# CAMERA.net
KiCad netlist of a schematic drawn in Altium Designer
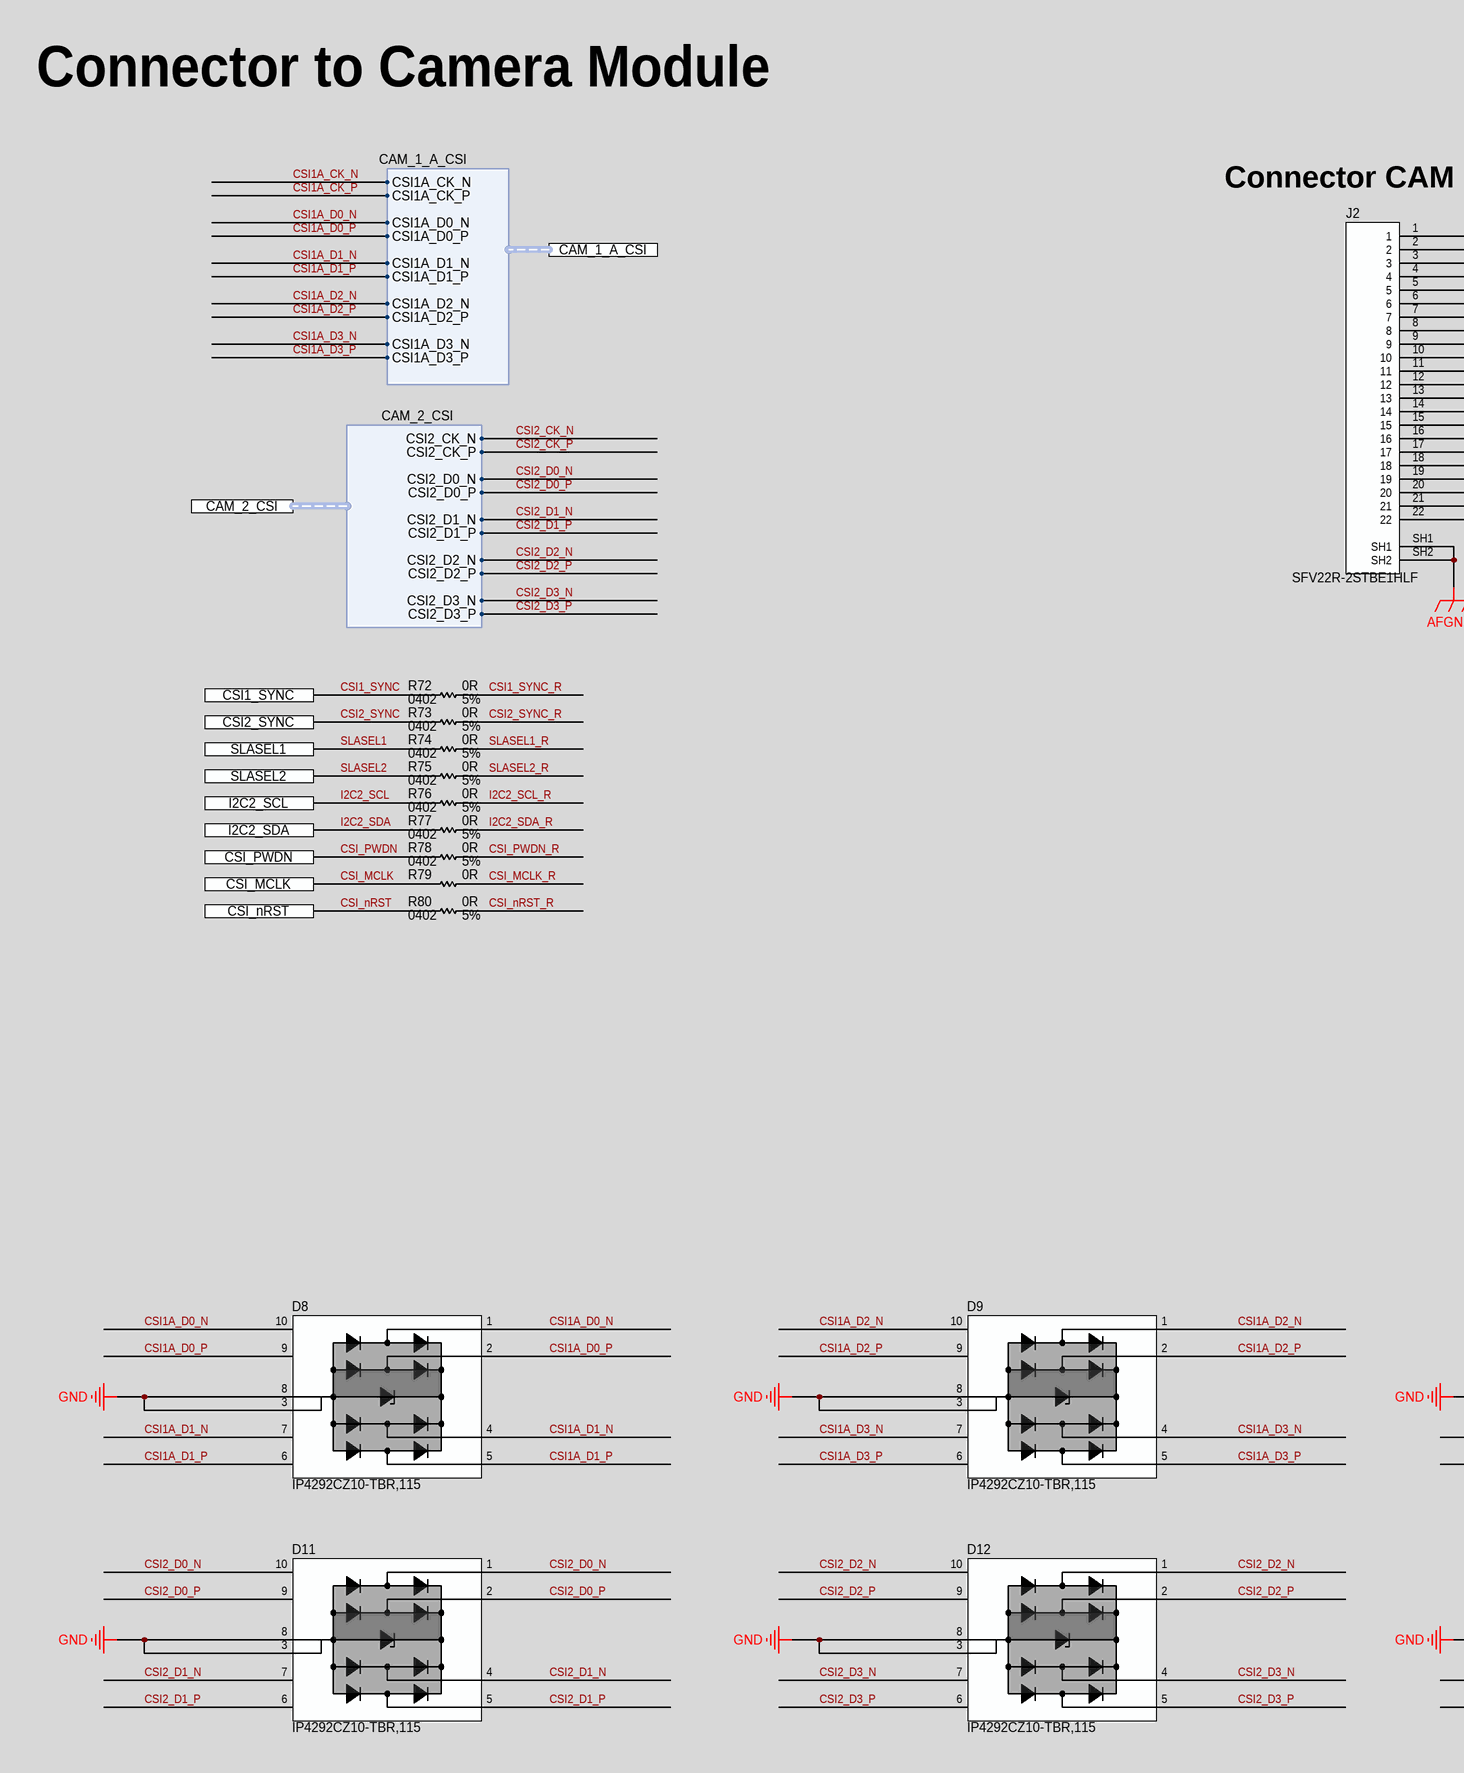
[diagram p0: CAMERA.SchDoc, left]
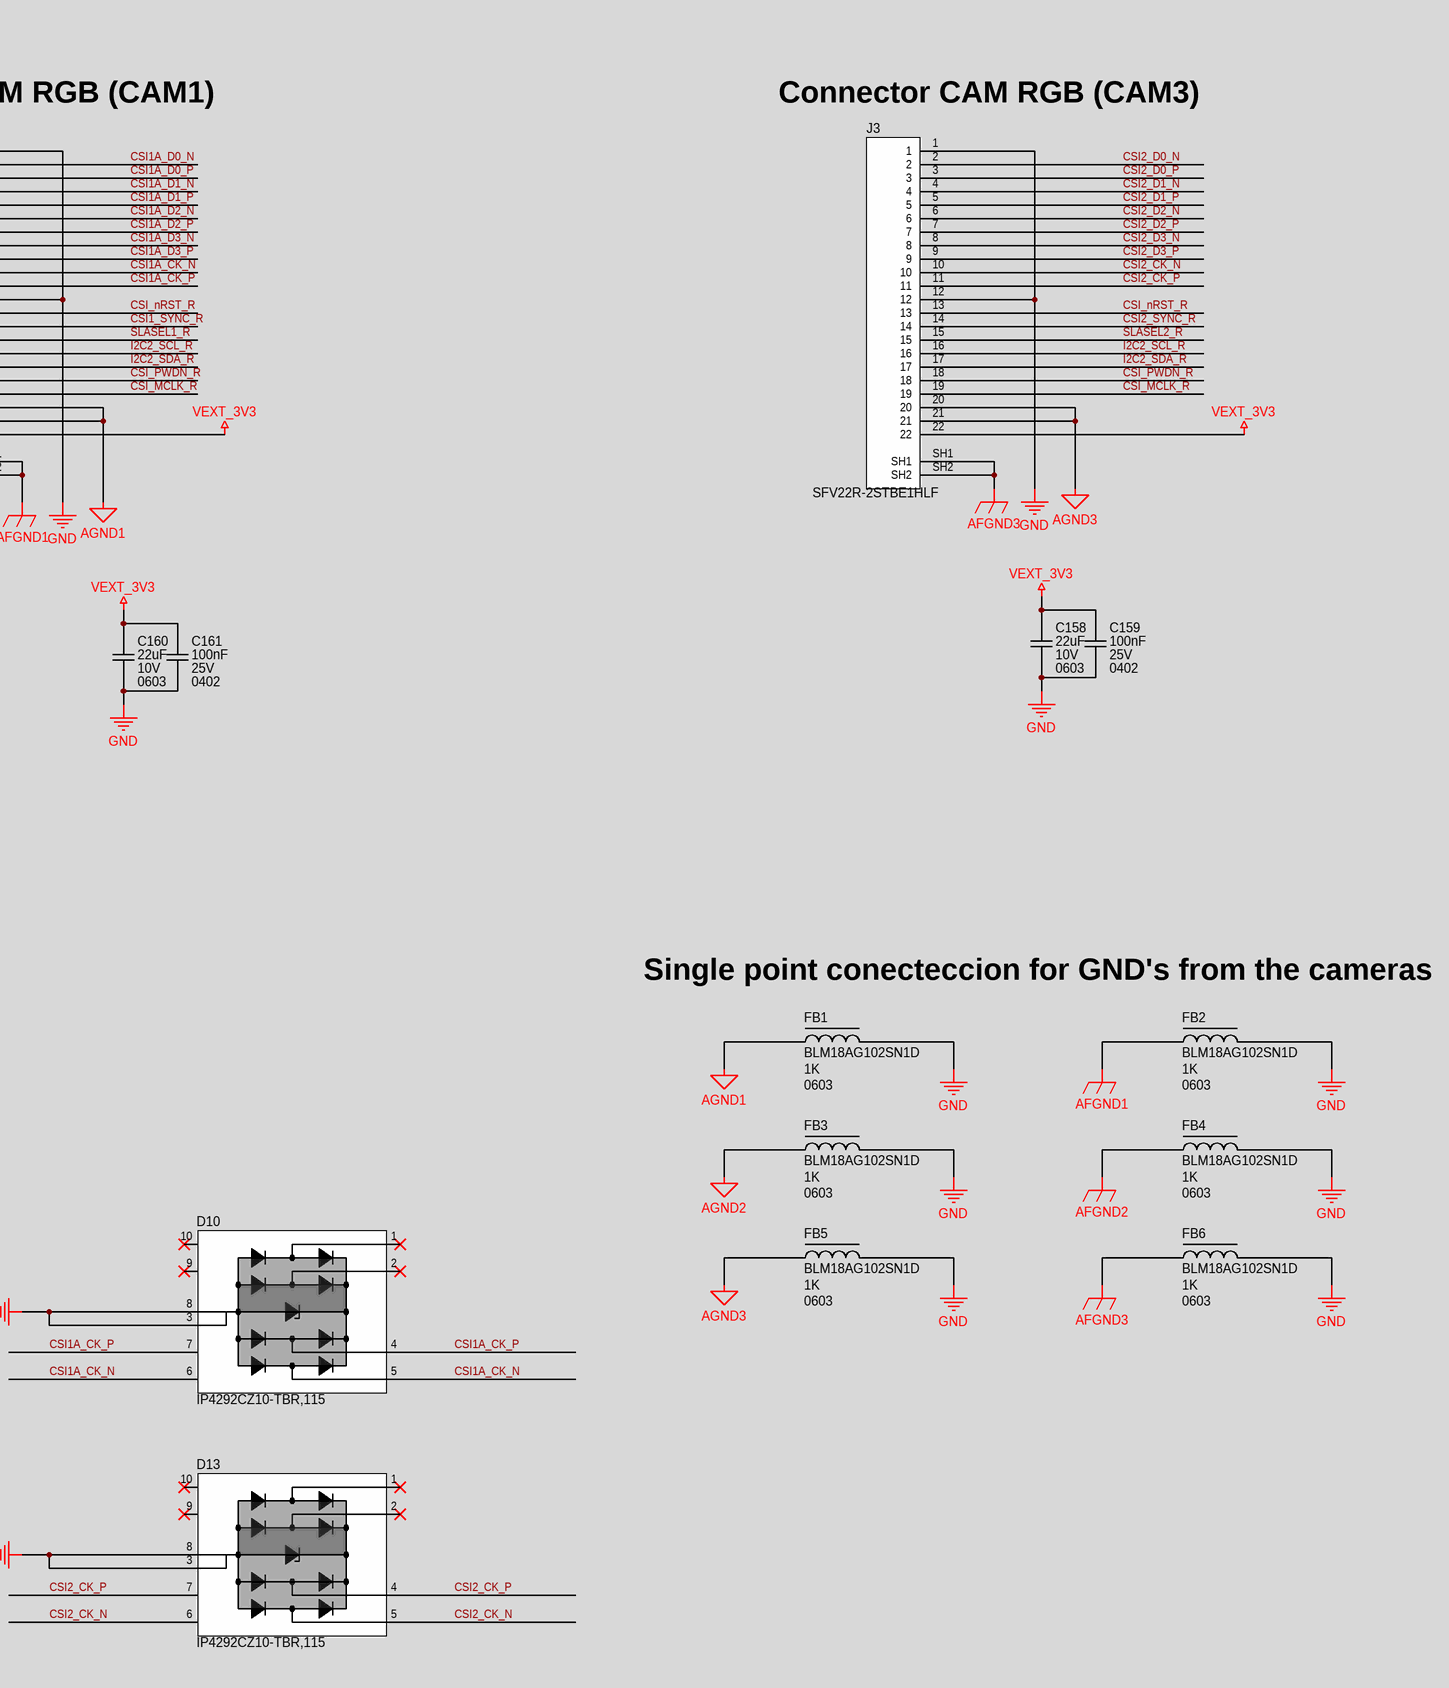
[diagram p1: CAMERA.SchDoc, right]

(export (version "E")
  (design (tool "Eeschema 10.0.6"))
  (components
    (comp (ref "C158")
      (value "C1608X5R1A226M080AC")
      (footprint "CAP_0603_CAPC1608X08N")
      (description "Multilayer Ceramic Capacitor, 22 uF, 10 V, ± 20%, X5R, 0603 [1608 Metric]")
      (fields
        (field (name "MANUFACTURER") "TDK")
        (field (name "TOLERANCE") "20%")
        (field (name "CAPACITANCE") "22uF")
        (field (name "VOLTAGE RATING") "10V")
        (field (name "CASE CODE (IMPERIAL)") "0603")
      )
      (libsource (lib "MGP Base_V1.0 RevA") (part "CAP_22UF_10V_X5R_0603"))
    )
    (comp (ref "C159")
      (value "CC0402KRX5R8BB104")
      (footprint "CAP_0402_CAPC1005X05N")
      (description "Multilayer Ceramic Capacitor, 0.1 uF, 25 V, ± 10%, X7R, 0402 [1005 Metric]")
      (fields
        (field (name "MANUFACTURER") "Yageo")
        (field (name "TOLERANCE") "10%")
        (field (name "CAPACITANCE") "100nF")
        (field (name "VOLTAGE RATING") "25V")
        (field (name "CASE/PACKAGE") "0402")
      )
      (libsource (lib "MGP Base_V1.0 RevA") (part "CAP_100NF_25V_X7R_0402"))
    )
    (comp (ref "C160")
      (value "C1608X5R1A226M080AC")
      (footprint "CAP_0603_CAPC1608X08N")
      (description "Multilayer Ceramic Capacitor, 22 uF, 10 V, ± 20%, X5R, 0603 [1608 Metric]")
      (fields
        (field (name "MANUFACTURER") "TDK")
        (field (name "TOLERANCE") "20%")
        (field (name "CAPACITANCE") "22uF")
        (field (name "VOLTAGE RATING") "10V")
        (field (name "CASE CODE (IMPERIAL)") "0603")
      )
      (libsource (lib "MGP Base_V1.0 RevA") (part "CAP_22UF_10V_X5R_0603"))
    )
    (comp (ref "C161")
      (value "CC0402KRX5R8BB104")
      (footprint "CAP_0402_CAPC1005X05N")
      (description "Multilayer Ceramic Capacitor, 0.1 uF, 25 V, ± 10%, X7R, 0402 [1005 Metric]")
      (fields
        (field (name "MANUFACTURER") "Yageo")
        (field (name "TOLERANCE") "10%")
        (field (name "CAPACITANCE") "100nF")
        (field (name "VOLTAGE RATING") "25V")
        (field (name "CASE/PACKAGE") "0402")
      )
      (libsource (lib "MGP Base_V1.0 RevA") (part "CAP_100NF_25V_X7R_0402"))
    )
    (comp (ref "D8")
      (value "IP4292CZ10-TBR,115")
      (footprint "DIO_TVS_SON50P100X250X50-10N")
      (description "IP4292CZ10 Series 4 Channel 4 V 0.55 pF ESD Protected TVS Diode - DFN2510A-10")
      (fields (field (name "MANUFACTURER") "Nexperia"))
      (libsource (lib "Electronic Devices_LIB") (part "DIO_TVS_4CH_4V_IP4292CZ10-TBR,115"))
    )
    (comp (ref "D9")
      (value "IP4292CZ10-TBR,115")
      (footprint "DIO_TVS_SON50P100X250X50-10N")
      (description "IP4292CZ10 Series 4 Channel 4 V 0.55 pF ESD Protected TVS Diode - DFN2510A-10")
      (fields (field (name "MANUFACTURER") "Nexperia"))
      (libsource (lib "Electronic Devices_LIB") (part "DIO_TVS_4CH_4V_IP4292CZ10-TBR,115"))
    )
    (comp (ref "D10")
      (value "IP4292CZ10-TBR,115")
      (footprint "DIO_TVS_SON50P100X250X50-10N")
      (description "IP4292CZ10 Series 4 Channel 4 V 0.55 pF ESD Protected TVS Diode - DFN2510A-10")
      (fields (field (name "MANUFACTURER") "Nexperia"))
      (libsource (lib "Electronic Devices_LIB") (part "DIO_TVS_4CH_4V_IP4292CZ10-TBR,115"))
    )
    (comp (ref "D11")
      (value "IP4292CZ10-TBR,115")
      (footprint "DIO_TVS_SON50P100X250X50-10N")
      (description "IP4292CZ10 Series 4 Channel 4 V 0.55 pF ESD Protected TVS Diode - DFN2510A-10")
      (fields (field (name "MANUFACTURER") "Nexperia"))
      (libsource (lib "Electronic Devices_LIB") (part "DIO_TVS_4CH_4V_IP4292CZ10-TBR,115"))
    )
    (comp (ref "D12")
      (value "IP4292CZ10-TBR,115")
      (footprint "DIO_TVS_SON50P100X250X50-10N")
      (description "IP4292CZ10 Series 4 Channel 4 V 0.55 pF ESD Protected TVS Diode - DFN2510A-10")
      (fields (field (name "MANUFACTURER") "Nexperia"))
      (libsource (lib "Electronic Devices_LIB") (part "DIO_TVS_4CH_4V_IP4292CZ10-TBR,115"))
    )
    (comp (ref "D13")
      (value "IP4292CZ10-TBR,115")
      (footprint "DIO_TVS_SON50P100X250X50-10N")
      (description "IP4292CZ10 Series 4 Channel 4 V 0.55 pF ESD Protected TVS Diode - DFN2510A-10")
      (fields (field (name "MANUFACTURER") "Nexperia"))
      (libsource (lib "Electronic Devices_LIB") (part "DIO_TVS_4CH_4V_IP4292CZ10-TBR,115"))
    )
    (comp (ref "FB1")
      (value "BLM18AG102SN1D")
      (footprint "IND_0603_INDC1608X08N")
      (description "Ferrite Beads Multi-Layer 1KOhm 25% 100MHz 450mA 500mOhm DCR 0603 T/R")
      (fields
        (field (name "MANUFACTURER") "Murata")
        (field (name "TOLERANCE") "25%")
        (field (name "IMPEDANCE") "1K")
        (field (name "CASE/PACKAGE") "0603")
      )
      (libsource (lib "Electronic Devices_LIB") (part "IND_FERRITA_1K_450mA_BLM18AG102SN1D"))
    )
    (comp (ref "FB2")
      (value "BLM18AG102SN1D")
      (footprint "IND_0603_INDC1608X08N")
      (description "Ferrite Beads Multi-Layer 1KOhm 25% 100MHz 450mA 500mOhm DCR 0603 T/R")
      (fields
        (field (name "MANUFACTURER") "Murata")
        (field (name "TOLERANCE") "25%")
        (field (name "IMPEDANCE") "1K")
        (field (name "CASE/PACKAGE") "0603")
      )
      (libsource (lib "Electronic Devices_LIB") (part "IND_FERRITA_1K_450mA_BLM18AG102SN1D"))
    )
    (comp (ref "FB3")
      (value "BLM18AG102SN1D")
      (footprint "IND_0603_INDC1608X08N")
      (description "Ferrite Beads Multi-Layer 1KOhm 25% 100MHz 450mA 500mOhm DCR 0603 T/R")
      (fields
        (field (name "MANUFACTURER") "Murata")
        (field (name "TOLERANCE") "25%")
        (field (name "IMPEDANCE") "1K")
        (field (name "CASE/PACKAGE") "0603")
      )
      (libsource (lib "Electronic Devices_LIB") (part "IND_FERRITA_1K_450mA_BLM18AG102SN1D"))
    )
    (comp (ref "FB4")
      (value "BLM18AG102SN1D")
      (footprint "IND_0603_INDC1608X08N")
      (description "Ferrite Beads Multi-Layer 1KOhm 25% 100MHz 450mA 500mOhm DCR 0603 T/R")
      (fields
        (field (name "MANUFACTURER") "Murata")
        (field (name "TOLERANCE") "25%")
        (field (name "IMPEDANCE") "1K")
        (field (name "CASE/PACKAGE") "0603")
      )
      (libsource (lib "Electronic Devices_LIB") (part "IND_FERRITA_1K_450mA_BLM18AG102SN1D"))
    )
    (comp (ref "FB5")
      (value "BLM18AG102SN1D")
      (footprint "IND_0603_INDC1608X08N")
      (description "Ferrite Beads Multi-Layer 1KOhm 25% 100MHz 450mA 500mOhm DCR 0603 T/R")
      (fields
        (field (name "MANUFACTURER") "Murata")
        (field (name "TOLERANCE") "25%")
        (field (name "IMPEDANCE") "1K")
        (field (name "CASE/PACKAGE") "0603")
      )
      (libsource (lib "Electronic Devices_LIB") (part "IND_FERRITA_1K_450mA_BLM18AG102SN1D"))
    )
    (comp (ref "FB6")
      (value "BLM18AG102SN1D")
      (footprint "IND_0603_INDC1608X08N")
      (description "Ferrite Beads Multi-Layer 1KOhm 25% 100MHz 450mA 500mOhm DCR 0603 T/R")
      (fields
        (field (name "MANUFACTURER") "Murata")
        (field (name "TOLERANCE") "25%")
        (field (name "IMPEDANCE") "1K")
        (field (name "CASE/PACKAGE") "0603")
      )
      (libsource (lib "Electronic Devices_LIB") (part "IND_FERRITA_1K_450mA_BLM18AG102SN1D"))
    )
    (comp (ref "J2")
      (value "SFV22R-2STBE1HLF")
      (footprint "CONN_FPC_AMPHENOL_SFV22R-2STBE1HLF")
      (description "Conn FFC/FPC Connector SKT 22 POS 0.5mm Solder RA SMD Embossed T/R")
      (fields (field (name "MANUFACTURER") "Amphenol ICC / FCI"))
      (libsource (lib "Electronic Devices_LIB") (part "CONN_FPC_22P_0.5mm_SFV22R-2STBE1HLF"))
    )
    (comp (ref "J3")
      (value "SFV22R-2STBE1HLF")
      (footprint "CONN_FPC_AMPHENOL_SFV22R-2STBE1HLF")
      (description "Conn FFC/FPC Connector SKT 22 POS 0.5mm Solder RA SMD Embossed T/R")
      (fields (field (name "MANUFACTURER") "Amphenol ICC / FCI"))
      (libsource (lib "Electronic Devices_LIB") (part "CONN_FPC_22P_0.5mm_SFV22R-2STBE1HLF"))
    )
    (comp (ref "R72")
      (value "ERJ-2GE0R00X")
      (footprint "RES_0402_RESC1005X04N")
      (description "SMD Chip Resistor, Jumper, 0 ohm, 100 mW, 0402 [1005 Metric], Thick Film, General Purpose")
      (fields
        (field (name "MANUFACTURER") "Panasonic")
        (field (name "CASE CODE (IMPERIAL)") "0402")
        (field (name "TOLERANCE") "5%")
        (field (name "RESISTANCE") "0R")
      )
      (libsource (lib "MGP Base_V1.0 RevA") (part "RES_0R_5%_100mW_0402"))
    )
    (comp (ref "R73")
      (value "ERJ-2GE0R00X")
      (footprint "RES_0402_RESC1005X04N")
      (description "SMD Chip Resistor, Jumper, 0 ohm, 100 mW, 0402 [1005 Metric], Thick Film, General Purpose")
      (fields
        (field (name "MANUFACTURER") "Panasonic")
        (field (name "CASE CODE (IMPERIAL)") "0402")
        (field (name "TOLERANCE") "5%")
        (field (name "RESISTANCE") "0R")
      )
      (libsource (lib "MGP Base_V1.0 RevA") (part "RES_0R_5%_100mW_0402"))
    )
    (comp (ref "R74")
      (value "ERJ-2GE0R00X")
      (footprint "RES_0402_RESC1005X04N")
      (description "SMD Chip Resistor, Jumper, 0 ohm, 100 mW, 0402 [1005 Metric], Thick Film, General Purpose")
      (fields
        (field (name "MANUFACTURER") "Panasonic")
        (field (name "CASE CODE (IMPERIAL)") "0402")
        (field (name "TOLERANCE") "5%")
        (field (name "RESISTANCE") "0R")
      )
      (libsource (lib "MGP Base_V1.0 RevA") (part "RES_0R_5%_100mW_0402"))
    )
    (comp (ref "R75")
      (value "ERJ-2GE0R00X")
      (footprint "RES_0402_RESC1005X04N")
      (description "SMD Chip Resistor, Jumper, 0 ohm, 100 mW, 0402 [1005 Metric], Thick Film, General Purpose")
      (fields
        (field (name "MANUFACTURER") "Panasonic")
        (field (name "CASE CODE (IMPERIAL)") "0402")
        (field (name "TOLERANCE") "5%")
        (field (name "RESISTANCE") "0R")
      )
      (libsource (lib "MGP Base_V1.0 RevA") (part "RES_0R_5%_100mW_0402"))
    )
    (comp (ref "R76")
      (value "ERJ-2GE0R00X")
      (footprint "RES_0402_RESC1005X04N")
      (description "SMD Chip Resistor, Jumper, 0 ohm, 100 mW, 0402 [1005 Metric], Thick Film, General Purpose")
      (fields
        (field (name "MANUFACTURER") "Panasonic")
        (field (name "CASE CODE (IMPERIAL)") "0402")
        (field (name "TOLERANCE") "5%")
        (field (name "RESISTANCE") "0R")
      )
      (libsource (lib "MGP Base_V1.0 RevA") (part "RES_0R_5%_100mW_0402"))
    )
    (comp (ref "R77")
      (value "ERJ-2GE0R00X")
      (footprint "RES_0402_RESC1005X04N")
      (description "SMD Chip Resistor, Jumper, 0 ohm, 100 mW, 0402 [1005 Metric], Thick Film, General Purpose")
      (fields
        (field (name "MANUFACTURER") "Panasonic")
        (field (name "CASE CODE (IMPERIAL)") "0402")
        (field (name "TOLERANCE") "5%")
        (field (name "RESISTANCE") "0R")
      )
      (libsource (lib "MGP Base_V1.0 RevA") (part "RES_0R_5%_100mW_0402"))
    )
    (comp (ref "R78")
      (value "ERJ-2GE0R00X")
      (footprint "RES_0402_RESC1005X04N")
      (description "SMD Chip Resistor, Jumper, 0 ohm, 100 mW, 0402 [1005 Metric], Thick Film, General Purpose")
      (fields
        (field (name "MANUFACTURER") "Panasonic")
        (field (name "CASE CODE (IMPERIAL)") "0402")
        (field (name "TOLERANCE") "5%")
        (field (name "RESISTANCE") "0R")
      )
      (libsource (lib "MGP Base_V1.0 RevA") (part "RES_0R_5%_100mW_0402"))
    )
    (comp (ref "R79")
      (value "ERJ-2GE0R00X")
      (footprint "RES_0402_RESC1005X04N")
      (description "SMD Chip Resistor, Jumper, 0 ohm, 100 mW, 0402 [1005 Metric], Thick Film, General Purpose")
      (fields (field (name "MANUFACTURER") "Panasonic") (field (name "RESISTANCE") "0R"))
      (libsource (lib "MGP Base_V1.0 RevA") (part "RES_0R_5%_100mW_0402"))
    )
    (comp (ref "R80")
      (value "ERJ-2GE0R00X")
      (footprint "RES_0402_RESC1005X04N")
      (description "SMD Chip Resistor, Jumper, 0 ohm, 100 mW, 0402 [1005 Metric], Thick Film, General Purpose")
      (fields
        (field (name "MANUFACTURER") "Panasonic")
        (field (name "CASE CODE (IMPERIAL)") "0402")
        (field (name "TOLERANCE") "5%")
        (field (name "RESISTANCE") "0R")
      )
      (libsource (lib "MGP Base_V1.0 RevA") (part "RES_0R_5%_100mW_0402"))
    )
  )
  (nets
    (net (code "3") (name "/CSI1A_CK_N") (class "Default")
      (node (ref "D10") (pin "5") (pinfunction "CH4_5") (pintype "passive"))
      (node (ref "D10") (pin "6") (pinfunction "NC1_6") (pintype "passive"))
      (node (ref "J2") (pin "10") (pinfunction "10_10") (pintype "passive"))
    )
    (net (code "4") (name "/CSI1A_CK_P") (class "Default")
      (node (ref "D10") (pin "4") (pinfunction "CH3_4") (pintype "passive"))
      (node (ref "D10") (pin "7") (pinfunction "NC2_7") (pintype "passive"))
      (node (ref "J2") (pin "11") (pinfunction "11_11") (pintype "passive"))
    )
    (net (code "5") (name "/CSI1A_D0_N") (class "Default")
      (node (ref "D8") (pin "1") (pinfunction "CH1_1") (pintype "passive"))
      (node (ref "D8") (pin "10") (pinfunction "NC4_10") (pintype "passive"))
      (node (ref "J2") (pin "2") (pinfunction "2_2") (pintype "passive"))
    )
    (net (code "6") (name "/CSI1A_D0_P") (class "Default")
      (node (ref "D8") (pin "2") (pinfunction "CH2_2") (pintype "passive"))
      (node (ref "D8") (pin "9") (pinfunction "NC3_9") (pintype "passive"))
      (node (ref "J2") (pin "3") (pinfunction "3_3") (pintype "passive"))
    )
    (net (code "7") (name "/CSI1A_D1_N") (class "Default")
      (node (ref "D8") (pin "4") (pinfunction "CH3_4") (pintype "passive"))
      (node (ref "D8") (pin "7") (pinfunction "NC2_7") (pintype "passive"))
      (node (ref "J2") (pin "4") (pinfunction "4_4") (pintype "passive"))
    )
    (net (code "8") (name "/CSI1A_D1_P") (class "Default")
      (node (ref "D8") (pin "5") (pinfunction "CH4_5") (pintype "passive"))
      (node (ref "D8") (pin "6") (pinfunction "NC1_6") (pintype "passive"))
      (node (ref "J2") (pin "5") (pinfunction "5_5") (pintype "passive"))
    )
    (net (code "9") (name "/CSI1A_D2_N") (class "Default")
      (node (ref "D9") (pin "1") (pinfunction "CH1_1") (pintype "passive"))
      (node (ref "D9") (pin "10") (pinfunction "NC4_10") (pintype "passive"))
      (node (ref "J2") (pin "6") (pinfunction "6_6") (pintype "passive"))
    )
    (net (code "10") (name "/CSI1A_D2_P") (class "Default")
      (node (ref "D9") (pin "2") (pinfunction "CH2_2") (pintype "passive"))
      (node (ref "D9") (pin "9") (pinfunction "NC3_9") (pintype "passive"))
      (node (ref "J2") (pin "7") (pinfunction "7_7") (pintype "passive"))
    )
    (net (code "11") (name "/CSI1A_D3_N") (class "Default")
      (node (ref "D9") (pin "4") (pinfunction "CH3_4") (pintype "passive"))
      (node (ref "D9") (pin "7") (pinfunction "NC2_7") (pintype "passive"))
      (node (ref "J2") (pin "8") (pinfunction "8_8") (pintype "passive"))
    )
    (net (code "12") (name "/CSI1A_D3_P") (class "Default")
      (node (ref "D9") (pin "5") (pinfunction "CH4_5") (pintype "passive"))
      (node (ref "D9") (pin "6") (pinfunction "NC1_6") (pintype "passive"))
      (node (ref "J2") (pin "9") (pinfunction "9_9") (pintype "passive"))
    )
    (net (code "13") (name "/CSI1_SYNC") (class "Default")
      (node (ref "R72") (pin "1") (pinfunction "1_1") (pintype "passive"))
    )
    (net (code "14") (name "/CSI1_SYNC_R") (class "Default")
      (node (ref "J2") (pin "14") (pinfunction "14_14") (pintype "passive"))
      (node (ref "R72") (pin "2") (pinfunction "2_2") (pintype "passive"))
    )
    (net (code "15") (name "/CSI2_CK_N") (class "Default")
      (node (ref "D13") (pin "5") (pinfunction "CH4_5") (pintype "passive"))
      (node (ref "D13") (pin "6") (pinfunction "NC1_6") (pintype "passive"))
      (node (ref "J3") (pin "10") (pinfunction "10_10") (pintype "passive"))
    )
    (net (code "16") (name "/CSI2_CK_P") (class "Default")
      (node (ref "D13") (pin "4") (pinfunction "CH3_4") (pintype "passive"))
      (node (ref "D13") (pin "7") (pinfunction "NC2_7") (pintype "passive"))
      (node (ref "J3") (pin "11") (pinfunction "11_11") (pintype "passive"))
    )
    (net (code "17") (name "/CSI2_D0_N") (class "Default")
      (node (ref "D11") (pin "1") (pinfunction "CH1_1") (pintype "passive"))
      (node (ref "D11") (pin "10") (pinfunction "NC4_10") (pintype "passive"))
      (node (ref "J3") (pin "2") (pinfunction "2_2") (pintype "passive"))
    )
    (net (code "18") (name "/CSI2_D0_P") (class "Default")
      (node (ref "D11") (pin "2") (pinfunction "CH2_2") (pintype "passive"))
      (node (ref "D11") (pin "9") (pinfunction "NC3_9") (pintype "passive"))
      (node (ref "J3") (pin "3") (pinfunction "3_3") (pintype "passive"))
    )
    (net (code "19") (name "/CSI2_D1_N") (class "Default")
      (node (ref "D11") (pin "4") (pinfunction "CH3_4") (pintype "passive"))
      (node (ref "D11") (pin "7") (pinfunction "NC2_7") (pintype "passive"))
      (node (ref "J3") (pin "4") (pinfunction "4_4") (pintype "passive"))
    )
    (net (code "20") (name "/CSI2_D1_P") (class "Default")
      (node (ref "D11") (pin "5") (pinfunction "CH4_5") (pintype "passive"))
      (node (ref "D11") (pin "6") (pinfunction "NC1_6") (pintype "passive"))
      (node (ref "J3") (pin "5") (pinfunction "5_5") (pintype "passive"))
    )
    (net (code "21") (name "/CSI2_D2_N") (class "Default")
      (node (ref "D12") (pin "1") (pinfunction "CH1_1") (pintype "passive"))
      (node (ref "D12") (pin "10") (pinfunction "NC4_10") (pintype "passive"))
      (node (ref "J3") (pin "6") (pinfunction "6_6") (pintype "passive"))
    )
    (net (code "22") (name "/CSI2_D2_P") (class "Default")
      (node (ref "D12") (pin "2") (pinfunction "CH2_2") (pintype "passive"))
      (node (ref "D12") (pin "9") (pinfunction "NC3_9") (pintype "passive"))
      (node (ref "J3") (pin "7") (pinfunction "7_7") (pintype "passive"))
    )
    (net (code "23") (name "/CSI2_D3_N") (class "Default")
      (node (ref "D12") (pin "4") (pinfunction "CH3_4") (pintype "passive"))
      (node (ref "D12") (pin "7") (pinfunction "NC2_7") (pintype "passive"))
      (node (ref "J3") (pin "8") (pinfunction "8_8") (pintype "passive"))
    )
    (net (code "24") (name "/CSI2_D3_P") (class "Default")
      (node (ref "D12") (pin "5") (pinfunction "CH4_5") (pintype "passive"))
      (node (ref "D12") (pin "6") (pinfunction "NC1_6") (pintype "passive"))
      (node (ref "J3") (pin "9") (pinfunction "9_9") (pintype "passive"))
    )
    (net (code "25") (name "/CSI2_SYNC") (class "Default")
      (node (ref "R73") (pin "1") (pinfunction "1_1") (pintype "passive"))
    )
    (net (code "26") (name "/CSI2_SYNC_R") (class "Default")
      (node (ref "J3") (pin "14") (pinfunction "14_14") (pintype "passive"))
      (node (ref "R73") (pin "2") (pinfunction "2_2") (pintype "passive"))
    )
    (net (code "27") (name "/CSI_MCLK") (class "Default")
      (node (ref "R79") (pin "1") (pinfunction "1_1") (pintype "passive"))
    )
    (net (code "28") (name "/CSI_MCLK_R") (class "Default")
      (node (ref "J2") (pin "19") (pinfunction "19_19") (pintype "passive"))
      (node (ref "J3") (pin "19") (pinfunction "19_19") (pintype "passive"))
      (node (ref "R79") (pin "2") (pinfunction "2_2") (pintype "passive"))
    )
    (net (code "29") (name "/CSI_PWDN") (class "Default")
      (node (ref "R78") (pin "1") (pinfunction "1_1") (pintype "passive"))
    )
    (net (code "30") (name "/CSI_PWDN_R") (class "Default")
      (node (ref "J2") (pin "18") (pinfunction "18_18") (pintype "passive"))
      (node (ref "J3") (pin "18") (pinfunction "18_18") (pintype "passive"))
      (node (ref "R78") (pin "2") (pinfunction "2_2") (pintype "passive"))
    )
    (net (code "31") (name "/CSI_nRST") (class "Default")
      (node (ref "R80") (pin "1") (pinfunction "1_1") (pintype "passive"))
    )
    (net (code "32") (name "/CSI_nRST_R") (class "Default")
      (node (ref "J2") (pin "13") (pinfunction "13_13") (pintype "passive"))
      (node (ref "J3") (pin "13") (pinfunction "13_13") (pintype "passive"))
      (node (ref "R80") (pin "2") (pinfunction "2_2") (pintype "passive"))
    )
    (net (code "33") (name "/I2C2_SCL") (class "Default")
      (node (ref "R76") (pin "1") (pinfunction "1_1") (pintype "passive"))
    )
    (net (code "34") (name "/I2C2_SCL_R") (class "Default")
      (node (ref "J2") (pin "16") (pinfunction "16_16") (pintype "passive"))
      (node (ref "J3") (pin "16") (pinfunction "16_16") (pintype "passive"))
      (node (ref "R76") (pin "2") (pinfunction "2_2") (pintype "passive"))
    )
    (net (code "35") (name "/I2C2_SDA") (class "Default")
      (node (ref "R77") (pin "1") (pinfunction "1_1") (pintype "passive"))
    )
    (net (code "36") (name "/I2C2_SDA_R") (class "Default")
      (node (ref "J2") (pin "17") (pinfunction "17_17") (pintype "passive"))
      (node (ref "J3") (pin "17") (pinfunction "17_17") (pintype "passive"))
      (node (ref "R77") (pin "2") (pinfunction "2_2") (pintype "passive"))
    )
    (net (code "37") (name "/SLASEL1") (class "Default")
      (node (ref "R74") (pin "1") (pinfunction "1_1") (pintype "passive"))
    )
    (net (code "38") (name "/SLASEL1_R") (class "Default")
      (node (ref "J2") (pin "15") (pinfunction "15_15") (pintype "passive"))
      (node (ref "R74") (pin "2") (pinfunction "2_2") (pintype "passive"))
    )
    (net (code "39") (name "/SLASEL2") (class "Default")
      (node (ref "R75") (pin "1") (pinfunction "1_1") (pintype "passive"))
    )
    (net (code "40") (name "/SLASEL2_R") (class "Default")
      (node (ref "J3") (pin "15") (pinfunction "15_15") (pintype "passive"))
      (node (ref "R75") (pin "2") (pinfunction "2_2") (pintype "passive"))
    )
    (net (code "43") (name "AFGND1") (class "Default")
      (node (ref "FB2") (pin "1") (pinfunction "1_1") (pintype "passive"))
      (node (ref "J2") (pin "SH1") (pinfunction "SH1_SH1") (pintype "passive"))
      (node (ref "J2") (pin "SH2") (pinfunction "SH2_SH2") (pintype "passive"))
    )
    (net (code "44") (name "AFGND2") (class "Default")
      (node (ref "FB4") (pin "1") (pinfunction "1_1") (pintype "passive"))
    )
    (net (code "45") (name "AFGND3") (class "Default")
      (node (ref "FB6") (pin "1") (pinfunction "1_1") (pintype "passive"))
      (node (ref "J3") (pin "SH1") (pinfunction "SH1_SH1") (pintype "passive"))
      (node (ref "J3") (pin "SH2") (pinfunction "SH2_SH2") (pintype "passive"))
    )
    (net (code "46") (name "AGND1") (class "Default")
      (node (ref "FB1") (pin "1") (pinfunction "1_1") (pintype "passive"))
      (node (ref "J2") (pin "20") (pinfunction "20_20") (pintype "passive"))
      (node (ref "J2") (pin "21") (pinfunction "21_21") (pintype "passive"))
    )
    (net (code "47") (name "AGND2") (class "Default")
      (node (ref "FB3") (pin "1") (pinfunction "1_1") (pintype "passive"))
    )
    (net (code "48") (name "AGND3") (class "Default")
      (node (ref "FB5") (pin "1") (pinfunction "1_1") (pintype "passive"))
      (node (ref "J3") (pin "20") (pinfunction "20_20") (pintype "passive"))
      (node (ref "J3") (pin "21") (pinfunction "21_21") (pintype "passive"))
    )
    (net (code "49") (name "GND") (class "Default")
      (node (ref "C158") (pin "1") (pinfunction "1_1") (pintype "passive"))
      (node (ref "C159") (pin "1") (pinfunction "1_1") (pintype "passive"))
      (node (ref "C160") (pin "1") (pinfunction "1_1") (pintype "passive"))
      (node (ref "C161") (pin "1") (pinfunction "1_1") (pintype "passive"))
      (node (ref "D10") (pin "3") (pinfunction "GND1_3") (pintype "power_in"))
      (node (ref "D10") (pin "8") (pinfunction "GND2_8") (pintype "power_in"))
      (node (ref "D11") (pin "3") (pinfunction "GND1_3") (pintype "power_in"))
      (node (ref "D11") (pin "8") (pinfunction "GND2_8") (pintype "power_in"))
      (node (ref "D12") (pin "3") (pinfunction "GND1_3") (pintype "power_in"))
      (node (ref "D12") (pin "8") (pinfunction "GND2_8") (pintype "power_in"))
      (node (ref "D13") (pin "3") (pinfunction "GND1_3") (pintype "power_in"))
      (node (ref "D13") (pin "8") (pinfunction "GND2_8") (pintype "power_in"))
      (node (ref "D8") (pin "3") (pinfunction "GND1_3") (pintype "power_in"))
      (node (ref "D8") (pin "8") (pinfunction "GND2_8") (pintype "power_in"))
      (node (ref "D9") (pin "3") (pinfunction "GND1_3") (pintype "power_in"))
      (node (ref "D9") (pin "8") (pinfunction "GND2_8") (pintype "power_in"))
      (node (ref "FB1") (pin "2") (pinfunction "2_2") (pintype "passive"))
      (node (ref "FB2") (pin "2") (pinfunction "2_2") (pintype "passive"))
      (node (ref "FB3") (pin "2") (pinfunction "2_2") (pintype "passive"))
      (node (ref "FB4") (pin "2") (pinfunction "2_2") (pintype "passive"))
      (node (ref "FB5") (pin "2") (pinfunction "2_2") (pintype "passive"))
      (node (ref "FB6") (pin "2") (pinfunction "2_2") (pintype "passive"))
      (node (ref "J2") (pin "1") (pinfunction "1_1") (pintype "passive"))
      (node (ref "J2") (pin "12") (pinfunction "12_12") (pintype "passive"))
      (node (ref "J3") (pin "1") (pinfunction "1_1") (pintype "passive"))
      (node (ref "J3") (pin "12") (pinfunction "12_12") (pintype "passive"))
    )
    (net (code "50") (name "VEXT_3V3") (class "Default")
      (node (ref "C158") (pin "2") (pinfunction "2_2") (pintype "passive"))
      (node (ref "C159") (pin "2") (pinfunction "2_2") (pintype "passive"))
      (node (ref "C160") (pin "2") (pinfunction "2_2") (pintype "passive"))
      (node (ref "C161") (pin "2") (pinfunction "2_2") (pintype "passive"))
      (node (ref "J2") (pin "22") (pinfunction "22_22") (pintype "passive"))
      (node (ref "J3") (pin "22") (pinfunction "22_22") (pintype "passive"))
    )
    (net (code "51") (name "unconnected-(D10-CH1-Pad1)") (class "Default")
      (node (ref "D10") (pin "1") (pinfunction "CH1_1") (pintype "passive+no_connect"))
    )
    (net (code "52") (name "unconnected-(D10-CH2-Pad2)") (class "Default")
      (node (ref "D10") (pin "2") (pinfunction "CH2_2") (pintype "passive+no_connect"))
    )
    (net (code "53") (name "unconnected-(D10-NC3-Pad9)") (class "Default")
      (node (ref "D10") (pin "9") (pinfunction "NC3_9") (pintype "passive+no_connect"))
    )
    (net (code "54") (name "unconnected-(D10-NC4-Pad10)") (class "Default")
      (node (ref "D10") (pin "10") (pinfunction "NC4_10") (pintype "passive+no_connect"))
    )
    (net (code "55") (name "unconnected-(D13-CH1-Pad1)") (class "Default")
      (node (ref "D13") (pin "1") (pinfunction "CH1_1") (pintype "passive+no_connect"))
    )
    (net (code "56") (name "unconnected-(D13-CH2-Pad2)") (class "Default")
      (node (ref "D13") (pin "2") (pinfunction "CH2_2") (pintype "passive+no_connect"))
    )
    (net (code "57") (name "unconnected-(D13-NC3-Pad9)") (class "Default")
      (node (ref "D13") (pin "9") (pinfunction "NC3_9") (pintype "passive+no_connect"))
    )
    (net (code "58") (name "unconnected-(D13-NC4-Pad10)") (class "Default")
      (node (ref "D13") (pin "10") (pinfunction "NC4_10") (pintype "passive+no_connect"))
    )
  )
)
